# nix3PowerFinal.net
KiCad netlist of a schematic drawn in EAGLE
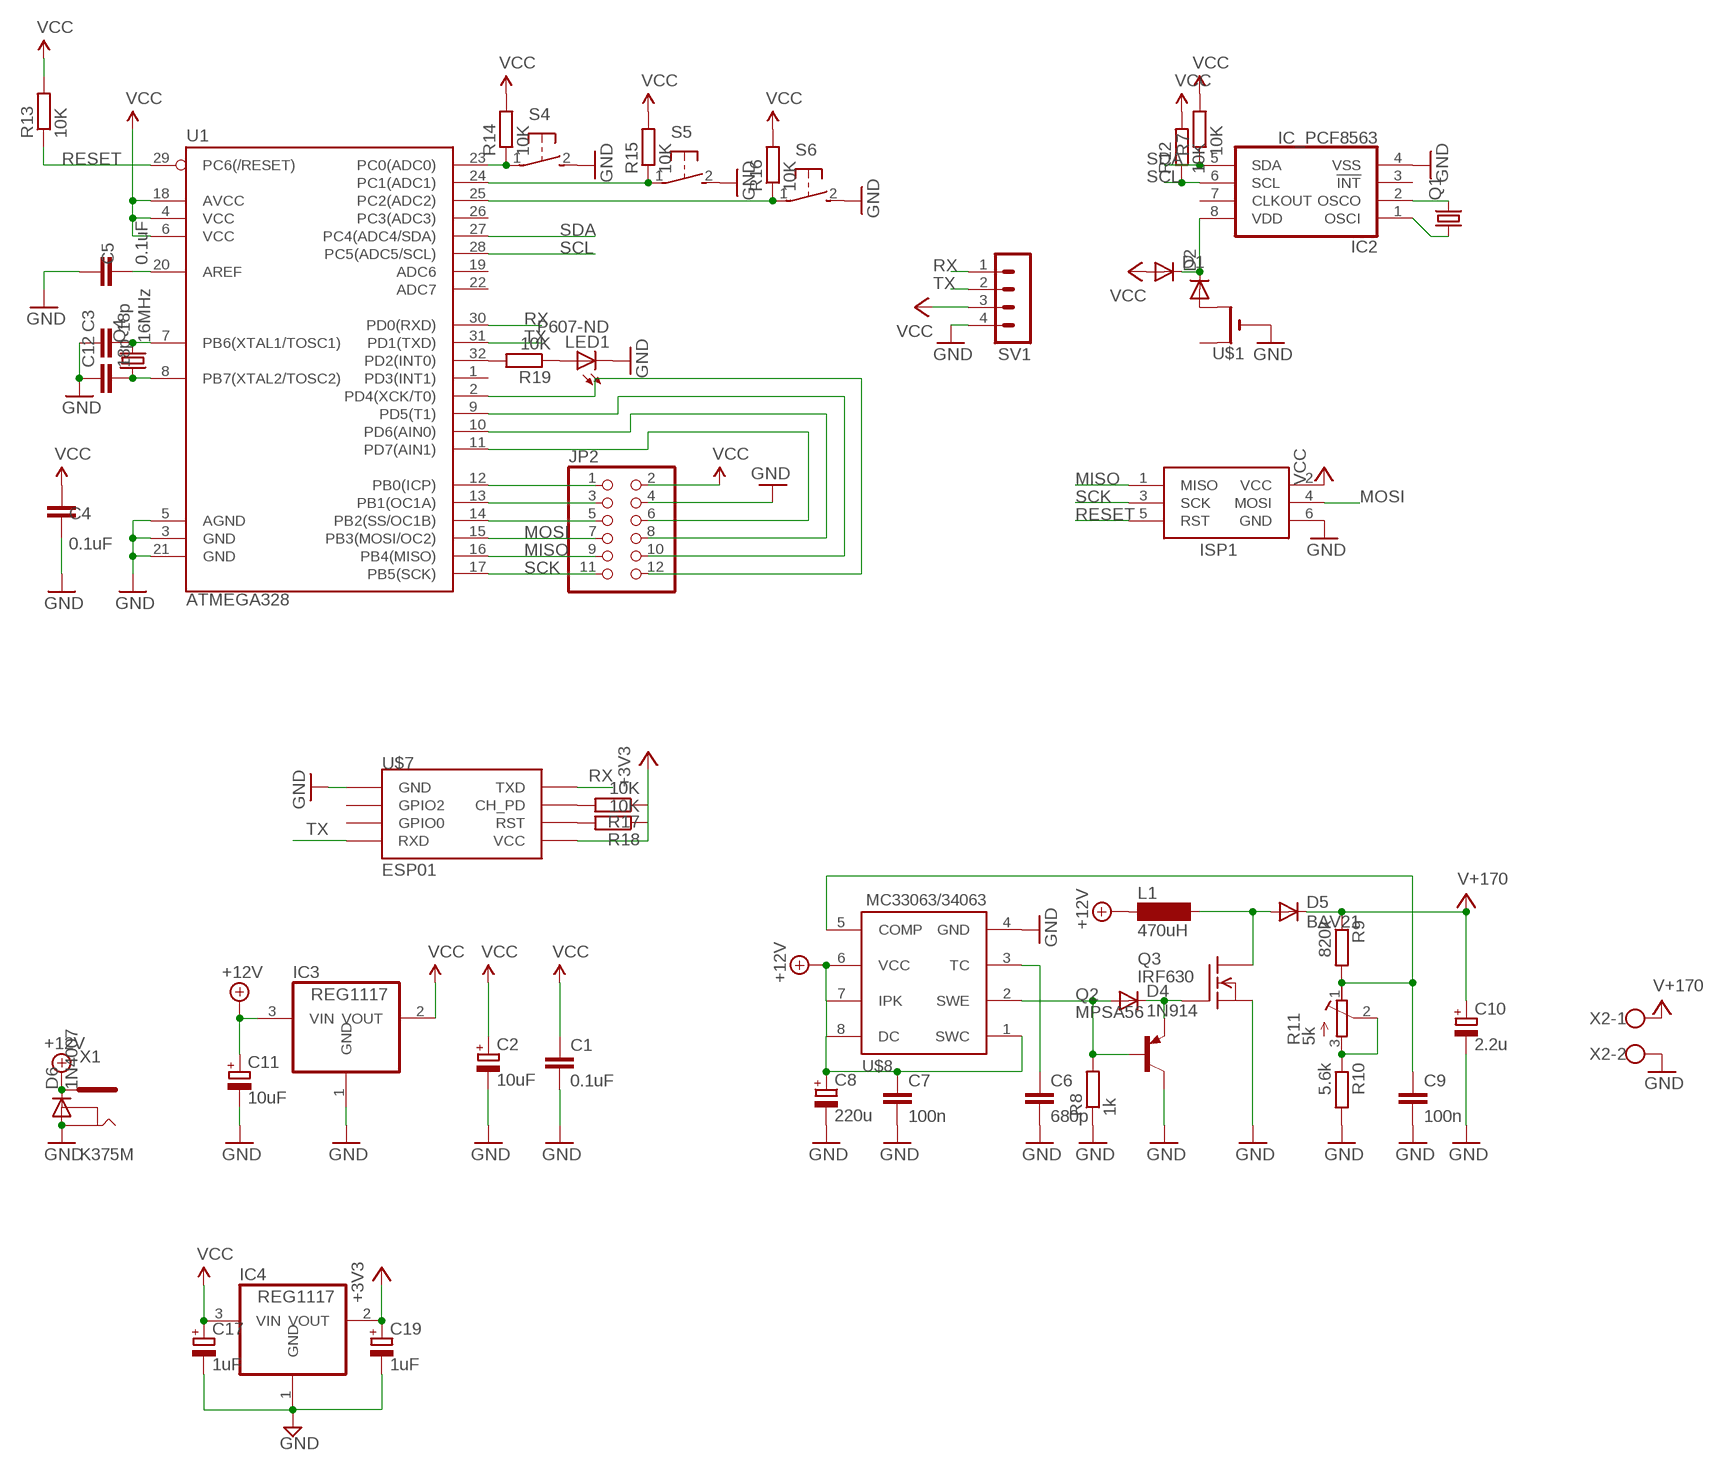
[diagram p0: schematic, sheet 1]

(export (version "E")
  (design (tool "Eeschema 10.0.6"))
  (components
    (comp (ref "C1")
      (value "0.1uF")
      (footprint "eagle-import:C0805")
      (libsource (lib "eagle-import") (part "C-EUC0805"))
    )
    (comp (ref "C2")
      (value "10uF")
      (footprint "eagle-import:E2,5-5")
      (libsource (lib "eagle-import") (part "CPOL-EUE2.5-5"))
    )
    (comp (ref "C3")
      (value "18p")
      (footprint "eagle-import:C0805")
      (libsource (lib "eagle-import") (part "C-EUC0805"))
    )
    (comp (ref "C4")
      (value "0.1uF")
      (footprint "eagle-import:C0805")
      (libsource (lib "eagle-import") (part "resistor_C-EUC0805"))
    )
    (comp (ref "C5")
      (value "0.1uF")
      (footprint "eagle-import:C0805")
      (libsource (lib "eagle-import") (part "resistor_C-EUC0805"))
    )
    (comp (ref "C6")
      (value "680p")
      (footprint "eagle-import:C050-025X075")
      (libsource (lib "eagle-import") (part "resistor_C-EU050-025X075"))
    )
    (comp (ref "C7")
      (value "100n")
      (footprint "eagle-import:C050-025X075")
      (libsource (lib "eagle-import") (part "resistor_C-EU050-025X075"))
    )
    (comp (ref "C8")
      (value "220u")
      (footprint "eagle-import:E3,5-8")
      (libsource (lib "eagle-import") (part "resistor_CPOL-EUE3.5-8"))
    )
    (comp (ref "C9")
      (value "100n")
      (footprint "eagle-import:C050-025X075")
      (libsource (lib "eagle-import") (part "resistor_C-EU050-025X075"))
    )
    (comp (ref "C10")
      (value "2.2u")
      (footprint "eagle-import:E3,5-8")
      (libsource (lib "eagle-import") (part "resistor_CPOL-EUE3.5-8"))
    )
    (comp (ref "C11")
      (value "10uF")
      (footprint "eagle-import:E2,5-5")
      (libsource (lib "eagle-import") (part "CPOL-EUE2.5-5"))
    )
    (comp (ref "C12")
      (value "18p")
      (footprint "eagle-import:C0805")
      (libsource (lib "eagle-import") (part "C-EUC0805"))
    )
    (comp (ref "C17")
      (value "1uF")
      (footprint "eagle-import:153CLV-0505")
      (libsource (lib "eagle-import") (part "CPOL-EU153CLV-0505"))
    )
    (comp (ref "C19")
      (value "1uF")
      (footprint "eagle-import:153CLV-0505")
      (libsource (lib "eagle-import") (part "CPOL-EU153CLV-0505"))
    )
    (comp (ref "D1")
      (value "DIODE-SOD80C")
      (footprint "eagle-import:SOD80C")
      (libsource (lib "eagle-import") (part "DIODE-SOD80C"))
    )
    (comp (ref "D2")
      (value "DIODE-SOD80C")
      (footprint "eagle-import:SOD80C")
      (libsource (lib "eagle-import") (part "DIODE-SOD80C"))
    )
    (comp (ref "D4")
      (value "1N914")
      (footprint "eagle-import:D-5")
      (libsource (lib "eagle-import") (part "DIODE-D-5"))
    )
    (comp (ref "D5")
      (value "BAV21")
      (footprint "eagle-import:D-5")
      (libsource (lib "eagle-import") (part "DIODE-D-5"))
    )
    (comp (ref "D6")
      (value "1N4007")
      (footprint "eagle-import:D-7.5")
      (libsource (lib "eagle-import") (part "DIODE-D-7.5"))
    )
    (comp (ref "IC2")
      (value "IC_PCF8563")
      (footprint "eagle-import:SO-8")
      (libsource (lib "eagle-import") (part "IC_PCF8563"))
    )
    (comp (ref "IC3")
      (value "REG1117")
      (footprint "eagle-import:SOT223")
      (libsource (lib "eagle-import") (part "REG1117"))
    )
    (comp (ref "IC4")
      (value "REG1117")
      (footprint "eagle-import:SOT223")
      (libsource (lib "eagle-import") (part "REG1117"))
    )
    (comp (ref "ISP1")
      (value "AVRISP-6")
      (footprint "eagle-import:AVRISP")
      (libsource (lib "eagle-import") (part "AVRISP-6"))
    )
    (comp (ref "JP2")
      (value "PINHD-2X6")
      (footprint "eagle-import:2X06")
      (libsource (lib "eagle-import") (part "PINHD-2X6"))
    )
    (comp (ref "L1")
      (value "470uH")
      (footprint "eagle-import:BS11")
      (libsource (lib "eagle-import") (part "BS11"))
    )
    (comp (ref "LED1")
      (value "P607-ND")
      (footprint "eagle-import:Q62902-B155")
      (libsource (lib "eagle-import") (part "LEDB155"))
    )
    (comp (ref "Q1")
      (value "CRYSTALTC38H")
      (footprint "eagle-import:TC38H")
      (libsource (lib "eagle-import") (part "CRYSTALTC38H"))
    )
    (comp (ref "Q2")
      (value "MPSA56")
      (footprint "eagle-import:TO92-CBE")
      (libsource (lib "eagle-import") (part "MPSA56"))
    )
    (comp (ref "Q3")
      (value "IRF630")
      (footprint "eagle-import:TO220")
      (libsource (lib "eagle-import") (part "IRF620"))
    )
    (comp (ref "Q4")
      (value "16MHz")
      (footprint "eagle-import:HC49U-V")
      (libsource (lib "eagle-import") (part "CRYSTALHC49U-V"))
    )
    (comp (ref "R7")
      (value "10K")
      (footprint "eagle-import:R0805")
      (libsource (lib "eagle-import") (part "R-EU_R0805"))
    )
    (comp (ref "R8")
      (value "1k")
      (footprint "eagle-import:0204_5")
      (libsource (lib "eagle-import") (part "R-EU_0204/5"))
    )
    (comp (ref "R9")
      (value "820k")
      (footprint "eagle-import:0204_5")
      (libsource (lib "eagle-import") (part "R-EU_0204/5"))
    )
    (comp (ref "R10")
      (value "5.6k")
      (footprint "eagle-import:0204_5")
      (libsource (lib "eagle-import") (part "R-EU_0204/5"))
    )
    (comp (ref "R11")
      (value "5k")
      (footprint "eagle-import:RTRIM43P")
      (libsource (lib "eagle-import") (part "R-TRIMM43P"))
    )
    (comp (ref "R12")
      (value "10K")
      (footprint "eagle-import:R0805")
      (libsource (lib "eagle-import") (part "R-EU_R0805"))
    )
    (comp (ref "R13")
      (value "10K")
      (footprint "eagle-import:R0805")
      (libsource (lib "eagle-import") (part "R-EU_R0805"))
    )
    (comp (ref "R14")
      (value "10K")
      (footprint "eagle-import:R0805")
      (libsource (lib "eagle-import") (part "R-EU_R0805"))
    )
    (comp (ref "R15")
      (value "10K")
      (footprint "eagle-import:R0805")
      (libsource (lib "eagle-import") (part "R-EU_R0805"))
    )
    (comp (ref "R16")
      (value "10K")
      (footprint "eagle-import:R0805")
      (libsource (lib "eagle-import") (part "R-EU_R0805"))
    )
    (comp (ref "R17")
      (value "10K")
      (footprint "eagle-import:R0805")
      (libsource (lib "eagle-import") (part "R-EU_R0805"))
    )
    (comp (ref "R18")
      (value "10K")
      (footprint "eagle-import:R0805")
      (libsource (lib "eagle-import") (part "R-EU_R0805"))
    )
    (comp (ref "R19")
      (value "10K")
      (footprint "eagle-import:R0805")
      (libsource (lib "eagle-import") (part "R-EU_R0805"))
    )
    (comp (ref "S4")
      (value "31-XX")
      (footprint "eagle-import:B3F-31XX")
      (fields (field (name "MPN") "B3F-3100"))
      (libsource (lib "eagle-import") (part "31-XX"))
    )
    (comp (ref "S5")
      (value "31-XX")
      (footprint "eagle-import:B3F-31XX")
      (fields (field (name "MPN") "B3F-3100"))
      (libsource (lib "eagle-import") (part "31-XX"))
    )
    (comp (ref "S6")
      (value "31-XX")
      (footprint "eagle-import:B3F-31XX")
      (fields (field (name "MPN") "B3F-3100"))
      (libsource (lib "eagle-import") (part "31-XX"))
    )
    (comp (ref "SV1")
      (value "MA04-1")
      (footprint "eagle-import:MA04-1")
      (libsource (lib "eagle-import") (part "MA04-1"))
    )
    (comp (ref "U$1")
      (value "CR2032THM")
      (footprint "eagle-import:CR2032-THRU")
      (libsource (lib "eagle-import") (part "CR2032THM"))
    )
    (comp (ref "U$7")
      (value "ESP01")
      (footprint "eagle-import:ESP01")
      (libsource (lib "eagle-import") (part "ESP01"))
    )
    (comp (ref "U$8")
      (value "MC33063/MC34063P")
      (footprint "eagle-import:DIL08")
      (libsource (lib "eagle-import") (part "MC33063/MC34063P"))
    )
    (comp (ref "U1")
      (value "ATMEGA328")
      (footprint "eagle-import:TQFP32-08")
      (libsource (lib "eagle-import") (part "ATMEGA168"))
    )
    (comp (ref "X1")
      (value "K375M")
      (footprint "eagle-import:K375M")
      (libsource (lib "eagle-import") (part "K375M"))
    )
    (comp (ref "X2")
      (value "W237-102")
      (footprint "eagle-import:W237-102")
      (fields (field (name "MPN") "237-102"))
      (libsource (lib "eagle-import") (part "W237-102"))
    )
  )
  (nets
    (net (code "1") (name "+3V3") (class "Default")
      (node (ref "C19") (pin "+") (pinfunction "+_+") (pintype "passive"))
      (node (ref "IC4") (pin "2") (pinfunction "VOUT_2") (pintype "output"))
      (node (ref "R17") (pin "1") (pinfunction "1_1") (pintype "passive"))
      (node (ref "R18") (pin "1") (pinfunction "1_1") (pintype "passive"))
      (node (ref "U$7") (pin "VCC") (pinfunction "VCC_VCC") (pintype "bidirectional"))
    )
    (net (code "2") (name "+12V") (class "Default")
      (node (ref "C11") (pin "+") (pinfunction "+_+") (pintype "passive"))
      (node (ref "C7") (pin "1") (pinfunction "1_1") (pintype "passive"))
      (node (ref "C8") (pin "+") (pinfunction "+_+") (pintype "passive"))
      (node (ref "D6") (pin "C") (pinfunction "C_C") (pintype "passive"))
      (node (ref "IC3") (pin "3") (pinfunction "VIN_3") (pintype "input"))
      (node (ref "L1") (pin "1") (pinfunction "1_1") (pintype "passive"))
      (node (ref "U$8") (pin "1") (pinfunction "SWC_1") (pintype "input"))
      (node (ref "U$8") (pin "6") (pinfunction "VCC_6") (pintype "power_in"))
      (node (ref "U$8") (pin "7") (pinfunction "IPK_7") (pintype "bidirectional"))
      (node (ref "U$8") (pin "8") (pinfunction "DC_8") (pintype "input"))
      (node (ref "X1") (pin "1") (pinfunction "1_1") (pintype "passive"))
    )
    (net (code "3") (name "GND") (class "Default")
      (node (ref "C1") (pin "2") (pinfunction "2_2") (pintype "passive"))
      (node (ref "C10") (pin "-") (pinfunction "-_-") (pintype "passive"))
      (node (ref "C11") (pin "-") (pinfunction "-_-") (pintype "passive"))
      (node (ref "C12") (pin "1") (pinfunction "1_1") (pintype "passive"))
      (node (ref "C17") (pin "-") (pinfunction "-_-") (pintype "passive"))
      (node (ref "C19") (pin "-") (pinfunction "-_-") (pintype "passive"))
      (node (ref "C2") (pin "-") (pinfunction "-_-") (pintype "passive"))
      (node (ref "C3") (pin "1") (pinfunction "1_1") (pintype "passive"))
      (node (ref "C4") (pin "1") (pinfunction "1_1") (pintype "passive"))
      (node (ref "C5") (pin "2") (pinfunction "2_2") (pintype "passive"))
      (node (ref "C6") (pin "2") (pinfunction "2_2") (pintype "passive"))
      (node (ref "C7") (pin "2") (pinfunction "2_2") (pintype "passive"))
      (node (ref "C8") (pin "-") (pinfunction "-_-") (pintype "passive"))
      (node (ref "C9") (pin "2") (pinfunction "2_2") (pintype "passive"))
      (node (ref "D6") (pin "A") (pinfunction "A_A") (pintype "passive"))
      (node (ref "IC2") (pin "4") (pinfunction "VSS_4") (pintype "bidirectional"))
      (node (ref "IC3") (pin "1") (pinfunction "GND_1") (pintype "power_in"))
      (node (ref "IC4") (pin "1") (pinfunction "GND_1") (pintype "power_in"))
      (node (ref "ISP1") (pin "6") (pinfunction "GND_6") (pintype "power_in"))
      (node (ref "JP2") (pin "4") (pinfunction "4_4") (pintype "passive"))
      (node (ref "LED1") (pin "K") (pinfunction "C_K") (pintype "passive"))
      (node (ref "Q2") (pin "C") (pinfunction "C_C") (pintype "passive"))
      (node (ref "Q3") (pin "3") (pinfunction "S_3") (pintype "passive"))
      (node (ref "R10") (pin "2") (pinfunction "2_2") (pintype "passive"))
      (node (ref "R8") (pin "1") (pinfunction "1_1") (pintype "passive"))
      (node (ref "S4") (pin "2") (pinfunction "S_2") (pintype "passive"))
      (node (ref "S5") (pin "2") (pinfunction "S_2") (pintype "passive"))
      (node (ref "S6") (pin "2") (pinfunction "S_2") (pintype "passive"))
      (node (ref "SV1") (pin "4") (pinfunction "4_4") (pintype "passive"))
      (node (ref "U$1") (pin "-") (pinfunction "-_-") (pintype "passive"))
      (node (ref "U$7") (pin "GND") (pinfunction "GND_GND") (pintype "bidirectional"))
      (node (ref "U$8") (pin "4") (pinfunction "GND_4") (pintype "power_in"))
      (node (ref "U1") (pin "21") (pinfunction "GND_21") (pintype "bidirectional"))
      (node (ref "U1") (pin "3") (pinfunction "GND_3") (pintype "bidirectional"))
      (node (ref "U1") (pin "5") (pinfunction "AGND_5") (pintype "bidirectional"))
      (node (ref "X1") (pin "2") (pinfunction "2_2") (pintype "passive"))
      (node (ref "X2") (pin "2") (pinfunction "KL_2") (pintype "passive"))
    )
    (net (code "4") (name "MISO") (class "Default")
      (node (ref "ISP1") (pin "1") (pinfunction "MISO_1") (pintype "input"))
      (node (ref "JP2") (pin "9") (pinfunction "9_9") (pintype "passive"))
      (node (ref "U1") (pin "16") (pinfunction "PB4(MISO)_16") (pintype "bidirectional"))
    )
    (net (code "5") (name "MOSI") (class "Default")
      (node (ref "ISP1") (pin "4") (pinfunction "MOSI_4") (pintype "output"))
      (node (ref "JP2") (pin "7") (pinfunction "7_7") (pintype "passive"))
      (node (ref "U1") (pin "15") (pinfunction "PB3(MOSI/OC2)_15") (pintype "bidirectional"))
    )
    (net (code "6") (name "Net-(IC2-OSCI)") (class "Default")
      (node (ref "IC2") (pin "1") (pinfunction "OSCI_1") (pintype "bidirectional"))
      (node (ref "Q1") (pin "1") (pinfunction "1_1") (pintype "passive"))
    )
    (net (code "7") (name "Net-(IC2-OSCO)") (class "Default")
      (node (ref "IC2") (pin "2") (pinfunction "OSCO_2") (pintype "bidirectional"))
      (node (ref "Q1") (pin "2") (pinfunction "2_2") (pintype "passive"))
    )
    (net (code "8") (name "Net-(IC2-VDD)") (class "Default")
      (node (ref "D1") (pin "C") (pinfunction "C_C") (pintype "passive"))
      (node (ref "D2") (pin "C") (pinfunction "C_C") (pintype "passive"))
      (node (ref "IC2") (pin "8") (pinfunction "VDD_8") (pintype "bidirectional"))
    )
    (net (code "9") (name "Net-(LED1-PadA)") (class "Default")
      (node (ref "LED1") (pin "A") (pinfunction "A_A") (pintype "passive"))
      (node (ref "R19") (pin "1") (pinfunction "1_1") (pintype "passive"))
    )
    (net (code "10") (name "Net-(Q3-D)") (class "Default")
      (node (ref "D5") (pin "A") (pinfunction "A_A") (pintype "passive"))
      (node (ref "L1") (pin "2") (pinfunction "2_2") (pintype "passive"))
      (node (ref "Q3") (pin "2") (pinfunction "D_2") (pintype "passive"))
    )
    (net (code "11") (name "Net-(Q3-G)") (class "Default")
      (node (ref "D4") (pin "C") (pinfunction "C_C") (pintype "passive"))
      (node (ref "Q2") (pin "E") (pinfunction "E_E") (pintype "passive"))
      (node (ref "Q3") (pin "1") (pinfunction "G_1") (pintype "passive"))
    )
    (net (code "12") (name "Net-(R11-A)") (class "Default")
      (node (ref "C9") (pin "1") (pinfunction "1_1") (pintype "passive"))
      (node (ref "R11") (pin "1") (pinfunction "A_1") (pintype "passive"))
      (node (ref "R9") (pin "2") (pinfunction "2_2") (pintype "passive"))
      (node (ref "U$8") (pin "5") (pinfunction "COMP_5") (pintype "input"))
    )
    (net (code "13") (name "Net-(R11-E)") (class "Default")
      (node (ref "R10") (pin "1") (pinfunction "1_1") (pintype "passive"))
      (node (ref "R11") (pin "2") (pinfunction "S_2") (pintype "passive"))
      (node (ref "R11") (pin "3") (pinfunction "E_3") (pintype "passive"))
    )
    (net (code "14") (name "Net-(R17-Pad2)") (class "Default")
      (node (ref "R17") (pin "2") (pinfunction "2_2") (pintype "passive"))
      (node (ref "U$7") (pin "CH_PD") (pinfunction "CH_PD_CH_PD") (pintype "bidirectional"))
    )
    (net (code "15") (name "Net-(R18-Pad2)") (class "Default")
      (node (ref "R18") (pin "2") (pinfunction "2_2") (pintype "passive"))
      (node (ref "U$7") (pin "RST") (pinfunction "RST_RST") (pintype "bidirectional"))
    )
    (net (code "16") (name "Net-(S4-P)") (class "Default")
      (node (ref "R14") (pin "1") (pinfunction "1_1") (pintype "passive"))
      (node (ref "S4") (pin "1") (pinfunction "P_1") (pintype "passive"))
      (node (ref "U1") (pin "23") (pinfunction "PC0(ADC0)_23") (pintype "bidirectional"))
    )
    (net (code "17") (name "Net-(S5-P)") (class "Default")
      (node (ref "R15") (pin "1") (pinfunction "1_1") (pintype "passive"))
      (node (ref "S5") (pin "1") (pinfunction "P_1") (pintype "passive"))
      (node (ref "U1") (pin "24") (pinfunction "PC1(ADC1)_24") (pintype "bidirectional"))
    )
    (net (code "18") (name "Net-(S6-P)") (class "Default")
      (node (ref "R16") (pin "1") (pinfunction "1_1") (pintype "passive"))
      (node (ref "S6") (pin "1") (pinfunction "P_1") (pintype "passive"))
      (node (ref "U1") (pin "25") (pinfunction "PC2(ADC2)_25") (pintype "bidirectional"))
    )
    (net (code "19") (name "Net-(U$1-+1)") (class "Default")
      (node (ref "D2") (pin "A") (pinfunction "A_A") (pintype "passive"))
      (node (ref "U$1") (pin "+2") (pinfunction "+1_+2") (pintype "passive"))
    )
    (net (code "20") (name "Net-(U$8-SWE)") (class "Default")
      (node (ref "D4") (pin "A") (pinfunction "A_A") (pintype "passive"))
      (node (ref "Q2") (pin "B") (pinfunction "B_B") (pintype "passive"))
      (node (ref "R8") (pin "2") (pinfunction "2_2") (pintype "passive"))
      (node (ref "U$8") (pin "2") (pinfunction "SWE_2") (pintype "input"))
    )
    (net (code "21") (name "Net-(U$8-TC)") (class "Default")
      (node (ref "C6") (pin "1") (pinfunction "1_1") (pintype "passive"))
      (node (ref "U$8") (pin "3") (pinfunction "TC_3") (pintype "input"))
    )
    (net (code "22") (name "Net-(U1-AREF)") (class "Default")
      (node (ref "C5") (pin "1") (pinfunction "1_1") (pintype "passive"))
      (node (ref "U1") (pin "20") (pinfunction "AREF_20") (pintype "bidirectional"))
    )
    (net (code "23") (name "Net-(U1-PB0(ICP))") (class "Default")
      (node (ref "JP2") (pin "1") (pinfunction "1_1") (pintype "passive"))
      (node (ref "U1") (pin "12") (pinfunction "PB0(ICP)_12") (pintype "bidirectional"))
    )
    (net (code "24") (name "Net-(U1-PB1(OC1A))") (class "Default")
      (node (ref "JP2") (pin "3") (pinfunction "3_3") (pintype "passive"))
      (node (ref "U1") (pin "13") (pinfunction "PB1(OC1A)_13") (pintype "bidirectional"))
    )
    (net (code "25") (name "Net-(U1-PB2(SS{slash}OC1B))") (class "Default")
      (node (ref "JP2") (pin "5") (pinfunction "5_5") (pintype "passive"))
      (node (ref "U1") (pin "14") (pinfunction "PB2(SS/OC1B)_14") (pintype "bidirectional"))
    )
    (net (code "26") (name "Net-(U1-PB6(XTAL1{slash}TOSC1))") (class "Default")
      (node (ref "C3") (pin "2") (pinfunction "2_2") (pintype "passive"))
      (node (ref "Q4") (pin "2") (pinfunction "2_2") (pintype "passive"))
      (node (ref "U1") (pin "7") (pinfunction "PB6(XTAL1/TOSC1)_7") (pintype "bidirectional"))
    )
    (net (code "27") (name "Net-(U1-PB7(XTAL2{slash}TOSC2))") (class "Default")
      (node (ref "C12") (pin "2") (pinfunction "2_2") (pintype "passive"))
      (node (ref "Q4") (pin "1") (pinfunction "1_1") (pintype "passive"))
      (node (ref "U1") (pin "8") (pinfunction "PB7(XTAL2/TOSC2)_8") (pintype "bidirectional"))
    )
    (net (code "28") (name "Net-(U1-PD2(INT0))") (class "Default")
      (node (ref "R19") (pin "2") (pinfunction "2_2") (pintype "passive"))
      (node (ref "U1") (pin "32") (pinfunction "PD2(INT0)_32") (pintype "bidirectional"))
    )
    (net (code "29") (name "Net-(U1-PD4(XCK{slash}T0))") (class "Default")
      (node (ref "JP2") (pin "12") (pinfunction "12_12") (pintype "passive"))
      (node (ref "U1") (pin "2") (pinfunction "PD4(XCK/T0)_2") (pintype "bidirectional"))
    )
    (net (code "30") (name "Net-(U1-PD5(T1))") (class "Default")
      (node (ref "JP2") (pin "10") (pinfunction "10_10") (pintype "passive"))
      (node (ref "U1") (pin "9") (pinfunction "PD5(T1)_9") (pintype "bidirectional"))
    )
    (net (code "31") (name "Net-(U1-PD6(AIN0))") (class "Default")
      (node (ref "JP2") (pin "8") (pinfunction "8_8") (pintype "passive"))
      (node (ref "U1") (pin "10") (pinfunction "PD6(AIN0)_10") (pintype "bidirectional"))
    )
    (net (code "32") (name "Net-(U1-PD7(AIN1))") (class "Default")
      (node (ref "JP2") (pin "6") (pinfunction "6_6") (pintype "passive"))
      (node (ref "U1") (pin "11") (pinfunction "PD7(AIN1)_11") (pintype "bidirectional"))
    )
    (net (code "33") (name "RESET") (class "Default")
      (node (ref "ISP1") (pin "5") (pinfunction "RST_5") (pintype "output"))
      (node (ref "R13") (pin "1") (pinfunction "1_1") (pintype "passive"))
      (node (ref "U1") (pin "29") (pinfunction "PC6(/RESET)_29") (pintype "bidirectional"))
    )
    (net (code "34") (name "RX") (class "Default")
      (node (ref "SV1") (pin "1") (pinfunction "1_1") (pintype "passive"))
      (node (ref "U$7") (pin "TX") (pinfunction "TXD_TX") (pintype "bidirectional"))
      (node (ref "U1") (pin "30") (pinfunction "PD0(RXD)_30") (pintype "bidirectional"))
    )
    (net (code "35") (name "SCK") (class "Default")
      (node (ref "ISP1") (pin "3") (pinfunction "SCK_3") (pintype "output"))
      (node (ref "JP2") (pin "11") (pinfunction "11_11") (pintype "passive"))
      (node (ref "U1") (pin "17") (pinfunction "PB5(SCK)_17") (pintype "bidirectional"))
    )
    (net (code "36") (name "SCL") (class "Default")
      (node (ref "IC2") (pin "6") (pinfunction "SCL_6") (pintype "bidirectional"))
      (node (ref "R12") (pin "1") (pinfunction "1_1") (pintype "passive"))
      (node (ref "U1") (pin "28") (pinfunction "PC5(ADC5/SCL)_28") (pintype "bidirectional"))
    )
    (net (code "37") (name "SDA") (class "Default")
      (node (ref "IC2") (pin "5") (pinfunction "SDA_5") (pintype "bidirectional"))
      (node (ref "R7") (pin "1") (pinfunction "1_1") (pintype "passive"))
      (node (ref "U1") (pin "27") (pinfunction "PC4(ADC4/SDA)_27") (pintype "bidirectional"))
    )
    (net (code "38") (name "TX") (class "Default")
      (node (ref "SV1") (pin "2") (pinfunction "2_2") (pintype "passive"))
      (node (ref "U$7") (pin "RX") (pinfunction "RXD_RX") (pintype "bidirectional"))
      (node (ref "U1") (pin "31") (pinfunction "PD1(TXD)_31") (pintype "bidirectional"))
    )
    (net (code "39") (name "V+") (class "Default")
      (node (ref "C10") (pin "+") (pinfunction "+_+") (pintype "passive"))
      (node (ref "D5") (pin "C") (pinfunction "C_C") (pintype "passive"))
      (node (ref "R9") (pin "1") (pinfunction "1_1") (pintype "passive"))
      (node (ref "X2") (pin "1") (pinfunction "KL_1") (pintype "passive"))
    )
    (net (code "40") (name "VCC") (class "Default")
      (node (ref "C1") (pin "1") (pinfunction "1_1") (pintype "passive"))
      (node (ref "C17") (pin "+") (pinfunction "+_+") (pintype "passive"))
      (node (ref "C2") (pin "+") (pinfunction "+_+") (pintype "passive"))
      (node (ref "C4") (pin "2") (pinfunction "2_2") (pintype "passive"))
      (node (ref "D1") (pin "A") (pinfunction "A_A") (pintype "passive"))
      (node (ref "IC3") (pin "2") (pinfunction "VOUT_2") (pintype "output"))
      (node (ref "IC4") (pin "3") (pinfunction "VIN_3") (pintype "input"))
      (node (ref "ISP1") (pin "2") (pinfunction "VCC_2") (pintype "power_in"))
      (node (ref "JP2") (pin "2") (pinfunction "2_2") (pintype "passive"))
      (node (ref "R12") (pin "2") (pinfunction "2_2") (pintype "passive"))
      (node (ref "R13") (pin "2") (pinfunction "2_2") (pintype "passive"))
      (node (ref "R14") (pin "2") (pinfunction "2_2") (pintype "passive"))
      (node (ref "R15") (pin "2") (pinfunction "2_2") (pintype "passive"))
      (node (ref "R16") (pin "2") (pinfunction "2_2") (pintype "passive"))
      (node (ref "R7") (pin "2") (pinfunction "2_2") (pintype "passive"))
      (node (ref "SV1") (pin "3") (pinfunction "3_3") (pintype "passive"))
      (node (ref "U1") (pin "18") (pinfunction "AVCC_18") (pintype "bidirectional"))
      (node (ref "U1") (pin "4") (pinfunction "VCC_4") (pintype "bidirectional"))
      (node (ref "U1") (pin "6") (pinfunction "VCC_6") (pintype "bidirectional"))
    )
    (net (code "41") (name "unconnected-(IC2-CLKOUT-Pad7)") (class "Default")
      (node (ref "IC2") (pin "7") (pinfunction "CLKOUT_7") (pintype "bidirectional"))
    )
    (net (code "42") (name "unconnected-(IC2-~{INT}-Pad3)") (class "Default")
      (node (ref "IC2") (pin "3") (pinfunction "~{INT}_3") (pintype "bidirectional"))
    )
    (net (code "43") (name "unconnected-(U$1-+-Pad+1)") (class "Default")
      (node (ref "U$1") (pin "+1") (pinfunction "+_+1") (pintype "passive"))
    )
    (net (code "44") (name "unconnected-(U$7-PadGPIO0)") (class "Default")
      (node (ref "U$7") (pin "GPIO0") (pinfunction "GPIO0_GPIO0") (pintype "bidirectional"))
    )
    (net (code "45") (name "unconnected-(U$7-PadGPIO2)") (class "Default")
      (node (ref "U$7") (pin "GPIO2") (pinfunction "GPIO2_GPIO2") (pintype "bidirectional"))
    )
    (net (code "46") (name "unconnected-(U1-ADC6-Pad19)") (class "Default")
      (node (ref "U1") (pin "19") (pinfunction "ADC6_19") (pintype "bidirectional"))
    )
    (net (code "47") (name "unconnected-(U1-ADC7-Pad22)") (class "Default")
      (node (ref "U1") (pin "22") (pinfunction "ADC7_22") (pintype "bidirectional"))
    )
    (net (code "48") (name "unconnected-(U1-PC3(ADC3)-Pad26)") (class "Default")
      (node (ref "U1") (pin "26") (pinfunction "PC3(ADC3)_26") (pintype "bidirectional"))
    )
    (net (code "49") (name "unconnected-(U1-PD3(INT1)-Pad1)") (class "Default")
      (node (ref "U1") (pin "1") (pinfunction "PD3(INT1)_1") (pintype "bidirectional"))
    )
    (net (code "50") (name "unconnected-(X1-Pad3)") (class "Default")
      (node (ref "X1") (pin "3") (pinfunction "3_3") (pintype "passive"))
    )
  )
)
